# FoodTag_Schematic.net
KiCad netlist of a schematic drawn in EasyEDA
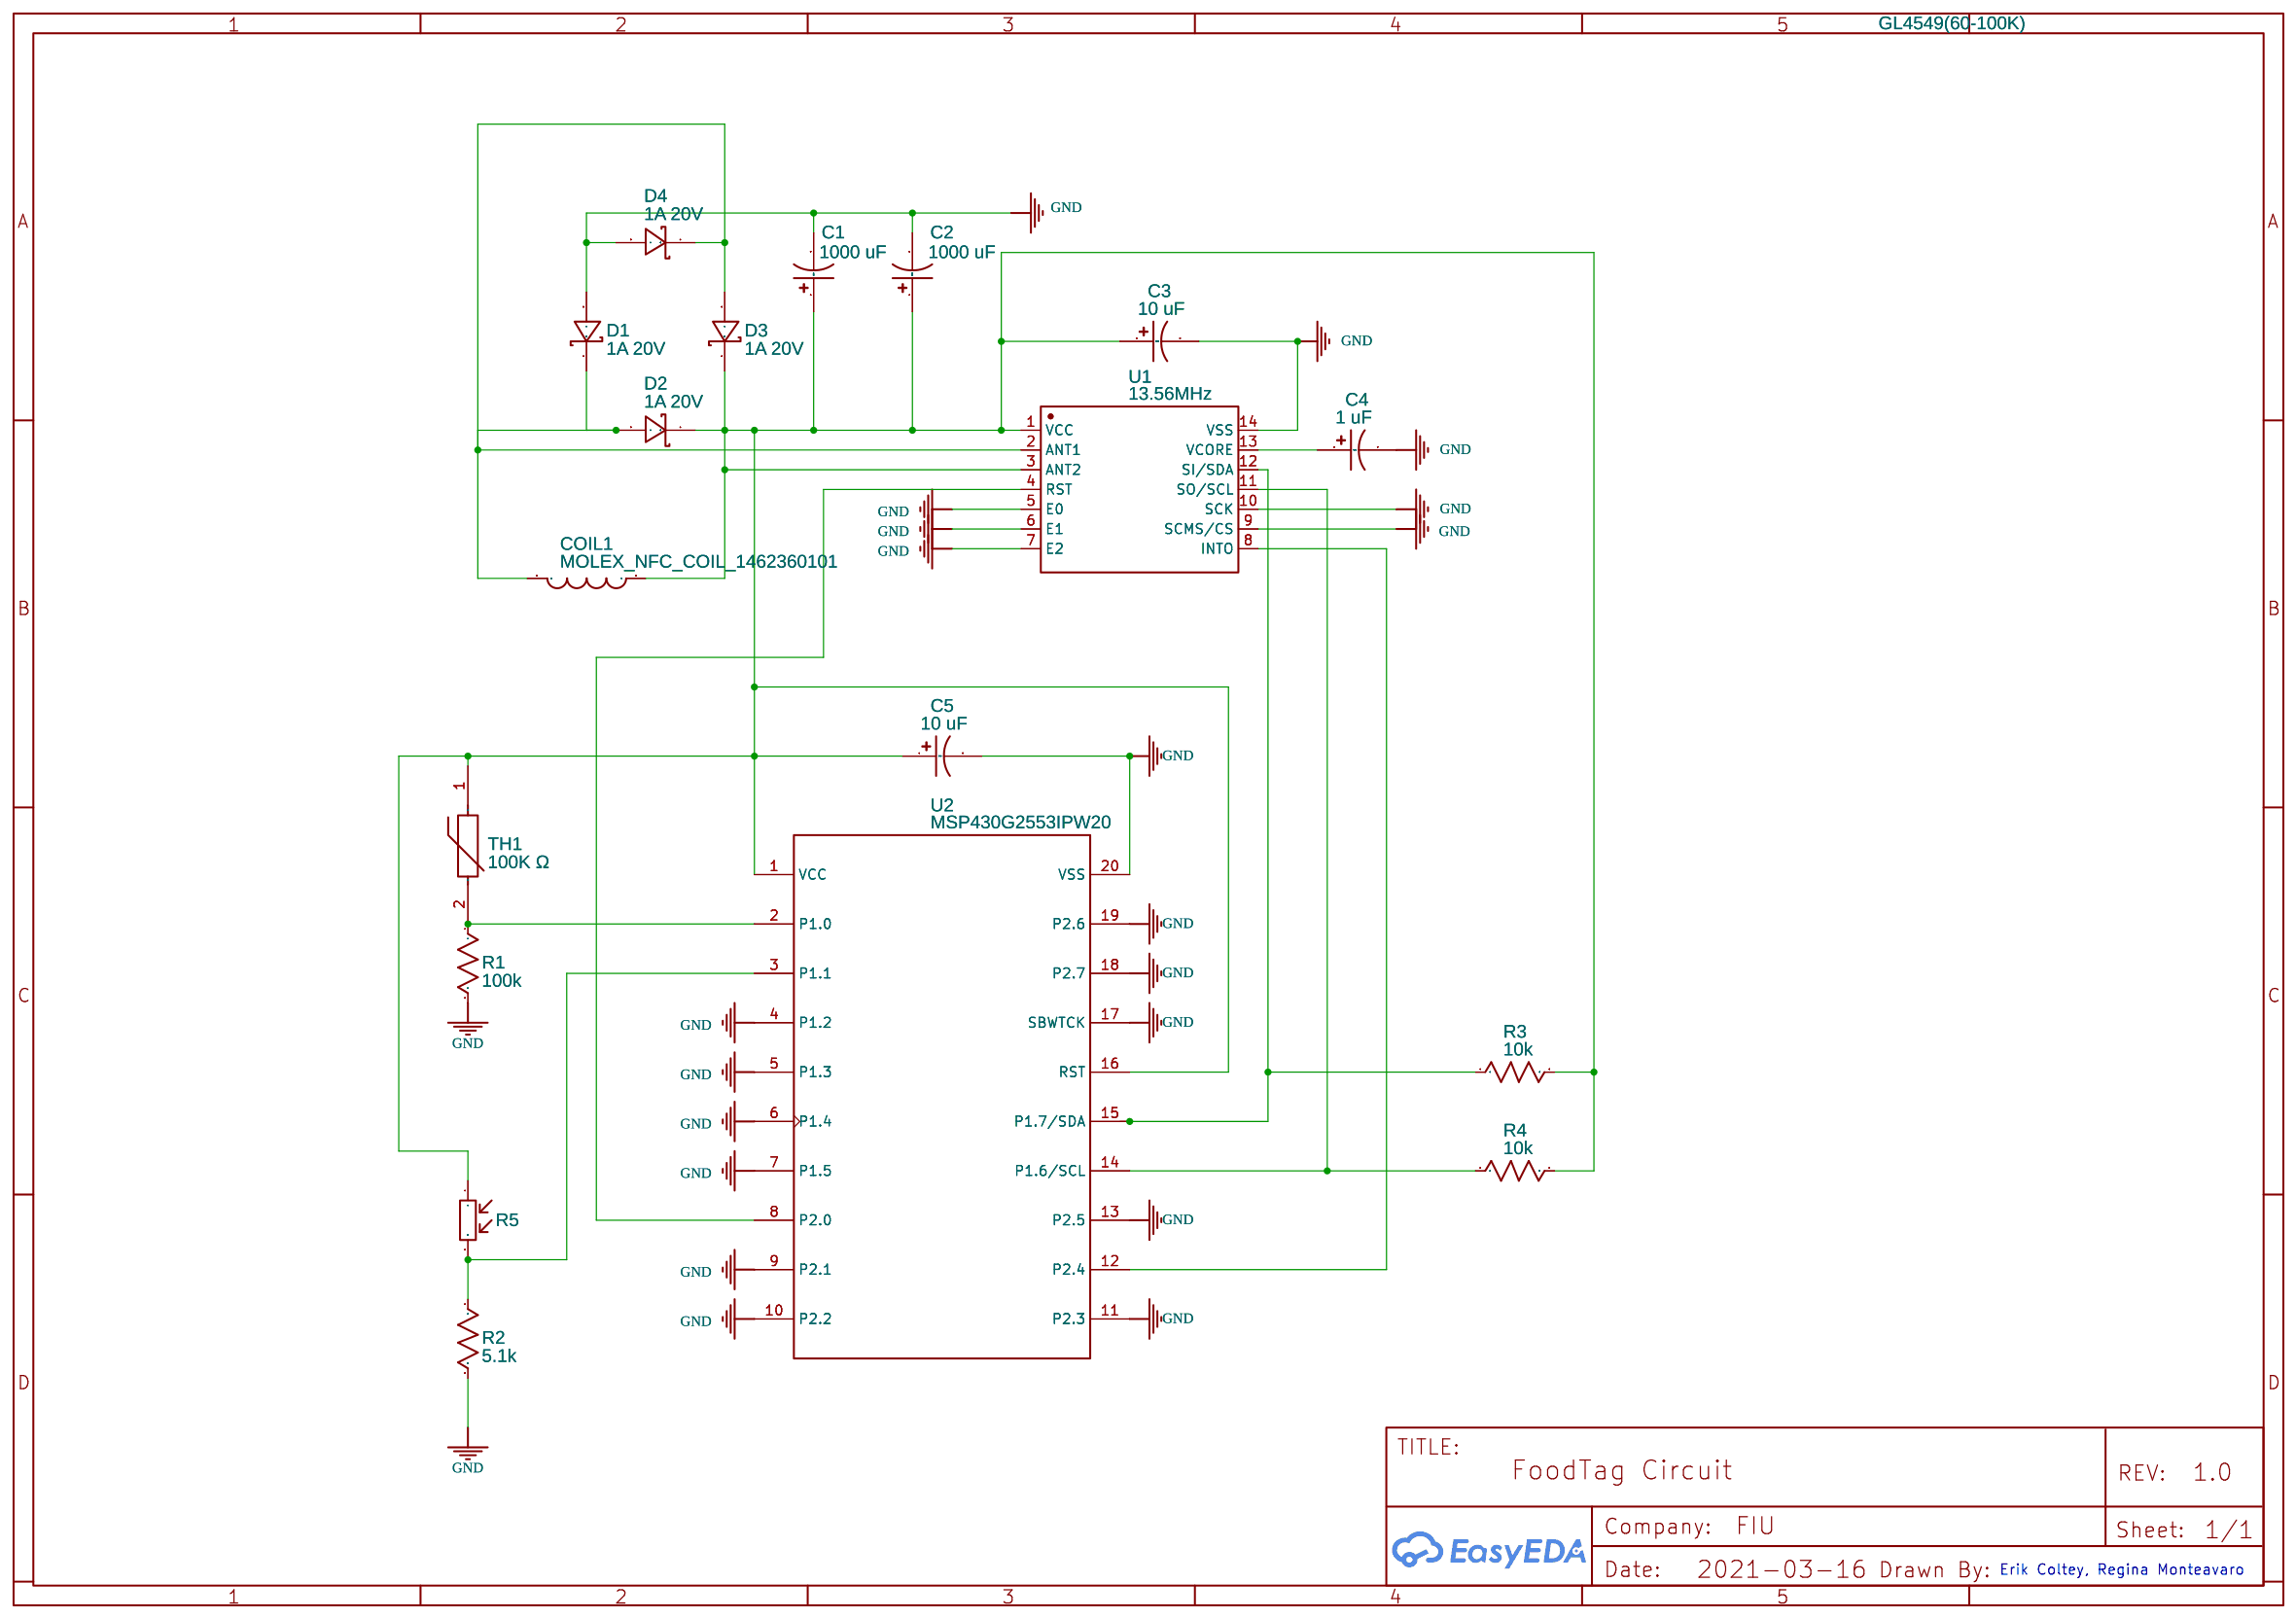
[diagram p0: schematic sheet]

(export (version "E")
  (design (tool "Eeschema 10.0.6"))
  (components
    (comp (ref "C1") (value "1000 uF") (libsource (lib "") (part "C_Tan_SMD_A_US_1")))
    (comp (ref "C2") (value "1000 uF") (libsource (lib "") (part "C_Tan_SMD_A_US_1")))
    (comp (ref "C3") (value "10 uF") (libsource (lib "") (part "C_Tan_SMD_A_US")))
    (comp (ref "C4") (value "1 uF") (libsource (lib "") (part "C_Tan_SMD_A_US")))
    (comp (ref "C5") (value "10 uF") (libsource (lib "") (part "C_Tan_SMD_A_US")))
    (comp (ref "COIL1")
      (value "MOLEX_NFC_COIL_1462360101")
      (libsource (lib "") (part "MOLEX_NFC_COIL_1462360101"))
    )
    (comp (ref "D1")
      (value "1A 20V")
      (fields
        (field (name "BOM_Manufacturer Part") "PMEG2010EA,115")
        (field (name "BOM_Supplier Part") "C193668")
      )
      (libsource (lib "") (part "PMEG2010EA,115"))
    )
    (comp (ref "D2")
      (value "1A 20V")
      (fields
        (field (name "BOM_Manufacturer Part") "PMEG2010EA,115")
        (field (name "BOM_Supplier Part") "C193668")
      )
      (libsource (lib "") (part "PMEG2010EA,115_1"))
    )
    (comp (ref "D3")
      (value "1A 20V")
      (fields
        (field (name "BOM_Manufacturer Part") "PMEG2010EA,115")
        (field (name "BOM_Supplier Part") "C193668")
      )
      (libsource (lib "") (part "PMEG2010EA,115"))
    )
    (comp (ref "D4")
      (value "1A 20V")
      (fields
        (field (name "BOM_Manufacturer Part") "PMEG2010EA,115")
        (field (name "BOM_Supplier Part") "C193668")
      )
      (libsource (lib "") (part "PMEG2010EA,115_1"))
    )
    (comp (ref "R1") (value "100k") (libsource (lib "") (part "R_0603_US_1")))
    (comp (ref "R2") (value "5.1k") (libsource (lib "") (part "R_0603_US_1")))
    (comp (ref "R3") (value "10k") (libsource (lib "") (part "R_0603_US")))
    (comp (ref "R4") (value "10k") (libsource (lib "") (part "R_0603_US")))
    (comp (ref "R5")
      (value "GL4549(60-100K)")
      (fields (field (name "BOM_Supplier Part") "C11297"))
      (libsource (lib "") (part "GL4549(60-100K)"))
    )
    (comp (ref "TH1")
      (value "100K Ω")
      (fields
        (field (name "BOM_Manufacturer Part") "NTCS0805E3104FXT")
        (field (name "BOM_Supplier Part") "C143680")
      )
      (libsource (lib "") (part "NTCS0805E3104FXT"))
    )
    (comp (ref "U1")
      (value "13.56MHz")
      (fields
        (field (name "BOM_Manufacturer Part") "RF430CL330HCPWR")
        (field (name "BOM_Supplier Part") "C130195")
      )
      (libsource (lib "") (part "RF430CL330HCPWR"))
    )
    (comp (ref "U2")
      (value "MSP430G2553IPW20")
      (fields (field (name "BOM_Supplier Part") "C53923"))
      (libsource (lib "") (part "MSP430G2553IPW20"))
    )
  )
  (nets
    (net (code "1") (name "GND") (class "Default")
      (node (ref "C1") (pin "2") (pinfunction "2_2") (pintype "unspecified"))
      (node (ref "C2") (pin "2") (pinfunction "2_2") (pintype "unspecified"))
      (node (ref "C3") (pin "2") (pinfunction "2_2") (pintype "unspecified"))
      (node (ref "C4") (pin "2") (pinfunction "2_2") (pintype "unspecified"))
      (node (ref "C5") (pin "2") (pinfunction "2_2") (pintype "unspecified"))
      (node (ref "D1") (pin "2") (pinfunction "A_2") (pintype "unspecified"))
      (node (ref "D4") (pin "2") (pinfunction "A_2") (pintype "unspecified"))
      (node (ref "R1") (pin "2") (pinfunction "2_2") (pintype "unspecified"))
      (node (ref "R2") (pin "2") (pinfunction "2_2") (pintype "unspecified"))
      (node (ref "U1") (pin "10") (pinfunction "SCK_10") (pintype "unspecified"))
      (node (ref "U1") (pin "14") (pinfunction "VSS_14") (pintype "unspecified"))
      (node (ref "U1") (pin "5") (pinfunction "E0_5") (pintype "unspecified"))
      (node (ref "U1") (pin "6") (pinfunction "E1_6") (pintype "unspecified"))
      (node (ref "U1") (pin "7") (pinfunction "E2_7") (pintype "unspecified"))
      (node (ref "U1") (pin "9") (pinfunction "SCMS/CS_9") (pintype "unspecified"))
      (node (ref "U2") (pin "10") (pinfunction "P2.2_10") (pintype "bidirectional"))
      (node (ref "U2") (pin "11") (pinfunction "P2.3_11") (pintype "bidirectional"))
      (node (ref "U2") (pin "13") (pinfunction "P2.5_13") (pintype "bidirectional"))
      (node (ref "U2") (pin "17") (pinfunction "SBWTCK_17") (pintype "unspecified"))
      (node (ref "U2") (pin "18") (pinfunction "P2.7_18") (pintype "bidirectional"))
      (node (ref "U2") (pin "19") (pinfunction "P2.6_19") (pintype "bidirectional"))
      (node (ref "U2") (pin "20") (pinfunction "VSS_20") (pintype "passive"))
      (node (ref "U2") (pin "4") (pinfunction "P1.2_4") (pintype "bidirectional"))
      (node (ref "U2") (pin "5") (pinfunction "P1.3_5") (pintype "bidirectional"))
      (node (ref "U2") (pin "6") (pinfunction "P1.4_6") (pintype "bidirectional"))
      (node (ref "U2") (pin "7") (pinfunction "P1.5_7") (pintype "bidirectional"))
      (node (ref "U2") (pin "9") (pinfunction "P2.1_9") (pintype "bidirectional"))
    )
    (net (code "2") (name "Net-(COIL1-1)") (class "Default")
      (node (ref "C1") (pin "1") (pinfunction "1_1") (pintype "unspecified"))
      (node (ref "C2") (pin "1") (pinfunction "1_1") (pintype "unspecified"))
      (node (ref "C3") (pin "1") (pinfunction "1_1") (pintype "unspecified"))
      (node (ref "C5") (pin "1") (pinfunction "1_1") (pintype "unspecified"))
      (node (ref "COIL1") (pin "P$1") (pinfunction "1_P$1") (pintype "bidirectional"))
      (node (ref "D2") (pin "1") (pinfunction "C_1") (pintype "unspecified"))
      (node (ref "D3") (pin "1") (pinfunction "C_1") (pintype "unspecified"))
      (node (ref "R3") (pin "2") (pinfunction "2_2") (pintype "unspecified"))
      (node (ref "R4") (pin "2") (pinfunction "2_2") (pintype "unspecified"))
      (node (ref "R5") (pin "1") (pinfunction "1_1") (pintype "input"))
      (node (ref "TH1") (pin "1") (pinfunction "1_1") (pintype "unspecified"))
      (node (ref "U1") (pin "1") (pinfunction "VCC_1") (pintype "unspecified"))
      (node (ref "U1") (pin "3") (pinfunction "ANT2_3") (pintype "unspecified"))
      (node (ref "U2") (pin "1") (pinfunction "VCC_1") (pintype "passive"))
      (node (ref "U2") (pin "16") (pinfunction "RST_16") (pintype "bidirectional"))
    )
    (net (code "3") (name "Net-(COIL1-2)") (class "Default")
      (node (ref "COIL1") (pin "P$2") (pinfunction "2_P$2") (pintype "bidirectional"))
      (node (ref "D1") (pin "1") (pinfunction "C_1") (pintype "unspecified"))
      (node (ref "D2") (pin "2") (pinfunction "A_2") (pintype "unspecified"))
      (node (ref "D3") (pin "2") (pinfunction "A_2") (pintype "unspecified"))
      (node (ref "D4") (pin "1") (pinfunction "C_1") (pintype "unspecified"))
      (node (ref "U1") (pin "2") (pinfunction "ANT1_2") (pintype "unspecified"))
    )
    (net (code "4") (name "Net-(U1-INTO)") (class "Default")
      (node (ref "U1") (pin "8") (pinfunction "INTO_8") (pintype "unspecified"))
      (node (ref "U2") (pin "12") (pinfunction "P2.4_12") (pintype "bidirectional"))
    )
    (net (code "5") (name "Net-(U1-RST)") (class "Default")
      (node (ref "U1") (pin "4") (pinfunction "RST_4") (pintype "unspecified"))
      (node (ref "U2") (pin "8") (pinfunction "P2.0_8") (pintype "bidirectional"))
    )
    (net (code "6") (name "Net-(U1-SI{slash}SDA)") (class "Default")
      (node (ref "R3") (pin "1") (pinfunction "1_1") (pintype "unspecified"))
      (node (ref "U1") (pin "12") (pinfunction "SI/SDA_12") (pintype "unspecified"))
      (node (ref "U2") (pin "15") (pinfunction "P1.7/SDA_15") (pintype "bidirectional"))
    )
    (net (code "7") (name "Net-(U1-SO{slash}SCL)") (class "Default")
      (node (ref "R4") (pin "1") (pinfunction "1_1") (pintype "unspecified"))
      (node (ref "U1") (pin "11") (pinfunction "SO/SCL_11") (pintype "unspecified"))
      (node (ref "U2") (pin "14") (pinfunction "P1.6/SCL_14") (pintype "bidirectional"))
    )
    (net (code "8") (name "Net-(U1-VCORE)") (class "Default")
      (node (ref "C4") (pin "1") (pinfunction "1_1") (pintype "unspecified"))
      (node (ref "U1") (pin "13") (pinfunction "VCORE_13") (pintype "unspecified"))
    )
    (net (code "9") (name "Net-(U2-P1.0)") (class "Default")
      (node (ref "R1") (pin "1") (pinfunction "1_1") (pintype "unspecified"))
      (node (ref "TH1") (pin "2") (pinfunction "2_2") (pintype "unspecified"))
      (node (ref "U2") (pin "2") (pinfunction "P1.0_2") (pintype "bidirectional"))
    )
    (net (code "10") (name "Net-(U2-P1.1)") (class "Default")
      (node (ref "R2") (pin "1") (pinfunction "1_1") (pintype "unspecified"))
      (node (ref "R5") (pin "2") (pinfunction "2_2") (pintype "input"))
      (node (ref "U2") (pin "3") (pinfunction "P1.1_3") (pintype "bidirectional"))
    )
  )
)
